# RoverMux.net
KiCad netlist of a schematic drawn in EAGLE
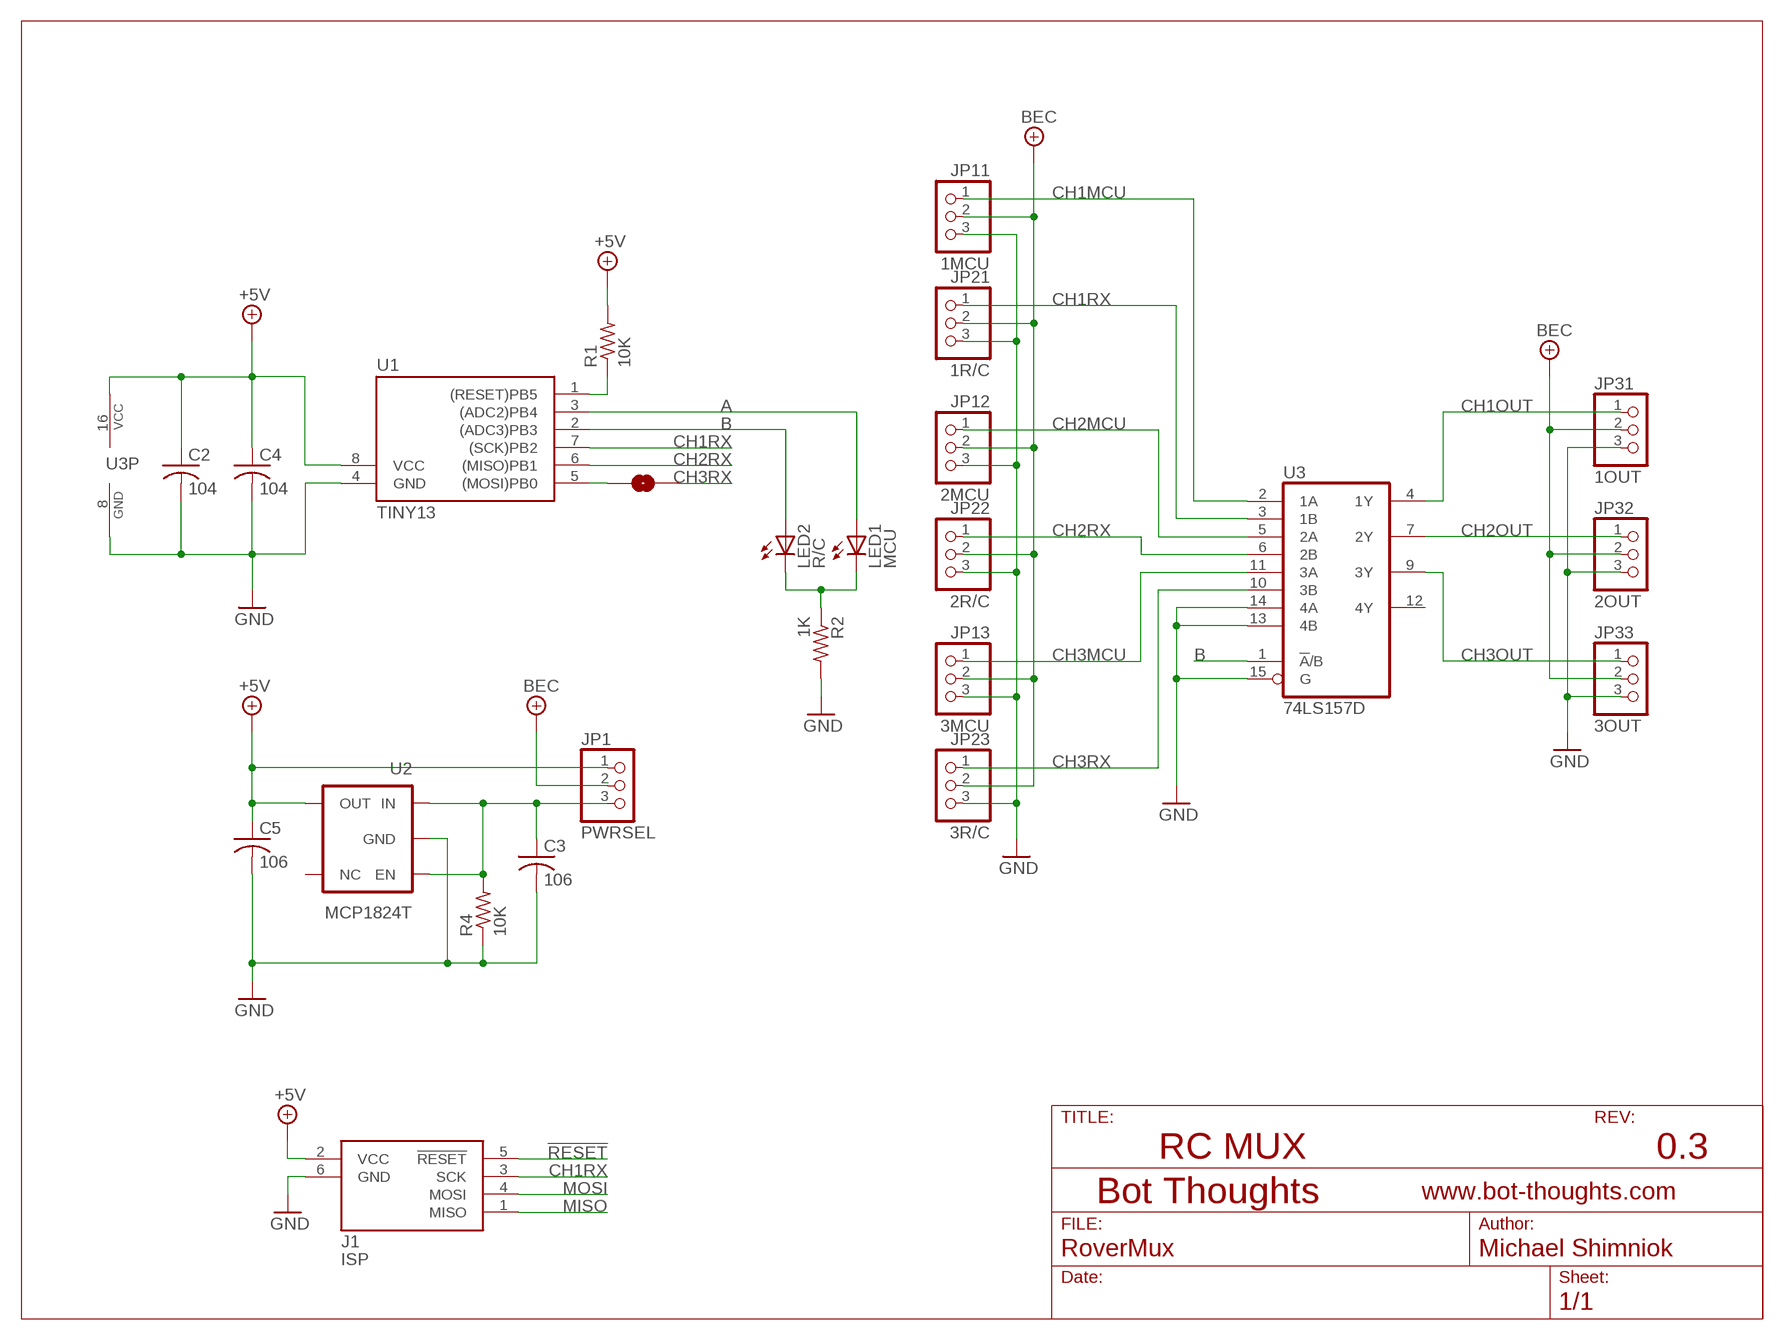
[diagram p0: schematic, sheet 1]

(export (version "E")
  (design (tool "Eeschema 10.0.6"))
  (components
    (comp (ref "C2")
      (value "104")
      (footprint "eagle-import:C0603")
      (fields (field (name "PARTNO") "C1608X7R1E104K080AA"))
      (libsource (lib "eagle-import") (part "C-USC0603"))
    )
    (comp (ref "C3")
      (value "106")
      (footprint "eagle-import:C0603")
      (fields (field (name "PARTNO") "CL10A106MP8NNNC"))
      (libsource (lib "eagle-import") (part "C-USC0603"))
    )
    (comp (ref "C4")
      (value "104")
      (footprint "eagle-import:C0603")
      (fields (field (name "PARTNO") "C1608X7R1E104K080AA"))
      (libsource (lib "eagle-import") (part "C-USC0603"))
    )
    (comp (ref "C5")
      (value "106")
      (footprint "eagle-import:C0603")
      (fields (field (name "PARTNO") "CL10A106MP8NNNC"))
      (libsource (lib "eagle-import") (part "C-USC0603"))
    )
    (comp (ref "J1")
      (value "ISP")
      (footprint "eagle-import:CON6P2R")
      (libsource (lib "eagle-import") (part "AVRISP6"))
    )
    (comp (ref "JP1")
      (value "PWRSEL")
      (footprint "eagle-import:1X03M")
      (libsource (lib "eagle-import") (part "PINHD-1X03_2.00"))
    )
    (comp (ref "JP11")
      (value "1MCU")
      (footprint "eagle-import:1X03-S")
      (libsource (lib "eagle-import") (part "PINHD-1X03_2.54-S"))
    )
    (comp (ref "JP12")
      (value "2MCU")
      (footprint "eagle-import:1X03-S")
      (libsource (lib "eagle-import") (part "PINHD-1X03_2.54-S"))
    )
    (comp (ref "JP13")
      (value "3MCU")
      (footprint "eagle-import:1X03-S")
      (libsource (lib "eagle-import") (part "PINHD-1X03_2.54-S"))
    )
    (comp (ref "JP21")
      (value "1R/C")
      (footprint "eagle-import:1X03-S")
      (libsource (lib "eagle-import") (part "PINHD-1X03_2.54-S"))
    )
    (comp (ref "JP22")
      (value "2R/C")
      (footprint "eagle-import:1X03-S")
      (libsource (lib "eagle-import") (part "PINHD-1X03_2.54-S"))
    )
    (comp (ref "JP23")
      (value "3R/C")
      (footprint "eagle-import:1X03-S")
      (libsource (lib "eagle-import") (part "PINHD-1X03_2.54-S"))
    )
    (comp (ref "JP31")
      (value "1OUT")
      (footprint "eagle-import:1X03-S")
      (libsource (lib "eagle-import") (part "PINHD-1X03_2.54-S"))
    )
    (comp (ref "JP32")
      (value "2OUT")
      (footprint "eagle-import:1X03-S")
      (libsource (lib "eagle-import") (part "PINHD-1X03_2.54-S"))
    )
    (comp (ref "JP33")
      (value "3OUT")
      (footprint "eagle-import:1X03-S")
      (libsource (lib "eagle-import") (part "PINHD-1X03_2.54-S"))
    )
    (comp (ref "LED1")
      (value "MCU")
      (footprint "eagle-import:CHIPLED_1206")
      (fields (field (name "PARTNO") "LH N974-KN-1"))
      (libsource (lib "eagle-import") (part "LEDCHIPLED_1206"))
    )
    (comp (ref "LED2")
      (value "R/C")
      (footprint "eagle-import:CHIPLED_1206")
      (fields (field (name "PARTNO") "LG N971-KN-1"))
      (libsource (lib "eagle-import") (part "LEDCHIPLED_1206"))
    )
    (comp (ref "R1")
      (value "10K")
      (footprint "eagle-import:R0603")
      (fields (field (name "PARTNO") "1622829-1"))
      (libsource (lib "eagle-import") (part "R-US_R0603"))
    )
    (comp (ref "R2")
      (value "1K")
      (footprint "eagle-import:R0603")
      (fields (field (name "PARTNO") "RC0603JR-07330RL"))
      (libsource (lib "eagle-import") (part "R-US_R0603"))
    )
    (comp (ref "R4")
      (value "10K")
      (footprint "eagle-import:R0603")
      (fields (field (name "PARTNO") "1622829-1"))
      (libsource (lib "eagle-import") (part "R-US_R0603"))
    )
    (comp (ref "SJ1")
      (value "CH3")
      (footprint "eagle-import:SJ_2S-NOTRACE")
      (libsource (lib "eagle-import") (part "SOLDERJUMPERNC2"))
    )
    (comp (ref "U1")
      (value "TINY13")
      (footprint "eagle-import:SO08")
      (fields (field (name "PARTNO") "ATTINY13A-SSH"))
      (libsource (lib "eagle-import") (part "TINY138S2"))
    )
    (comp (ref "U2")
      (value "MCP1824T")
      (footprint "eagle-import:SOT23-5")
      (fields (field (name "PARTNO") "MCP1824T-5002E/OT"))
      (libsource (lib "eagle-import") (part "MCP1801"))
    )
    (comp (ref "U3")
      (value "74LS157D")
      (footprint "eagle-import:SO16")
      (fields (field (name "PARTNO") "74HCT157D,652"))
      (libsource (lib "eagle-import") (part "74157DLS"))
    )
  )
  (nets
    (net (code "1") (name "+5V") (class "Default")
      (node (ref "C2") (pin "1") (pinfunction "1_1") (pintype "passive"))
      (node (ref "C4") (pin "1") (pinfunction "1_1") (pintype "passive"))
      (node (ref "C5") (pin "1") (pinfunction "1_1") (pintype "passive"))
      (node (ref "J1") (pin "2") (pinfunction "VCC_2") (pintype "power_in"))
      (node (ref "JP1") (pin "1") (pinfunction "1_1") (pintype "passive"))
      (node (ref "R1") (pin "2") (pinfunction "2_2") (pintype "passive"))
      (node (ref "U1") (pin "8") (pinfunction "VCC_8") (pintype "power_in"))
      (node (ref "U2") (pin "5") (pinfunction "OUT_5") (pintype "passive"))
      (node (ref "U3") (pin "16") (pinfunction "VCC_16") (pintype "power_in"))
    )
    (net (code "2") (name "/A") (class "Default")
      (node (ref "LED1") (pin "A") (pinfunction "A_A") (pintype "passive"))
      (node (ref "U1") (pin "3") (pinfunction "(ADC2)PB4_3") (pintype "bidirectional"))
    )
    (net (code "3") (name "/B") (class "Default")
      (node (ref "LED2") (pin "A") (pinfunction "A_A") (pintype "passive"))
      (node (ref "U1") (pin "2") (pinfunction "(ADC3)PB3_2") (pintype "bidirectional"))
      (node (ref "U3") (pin "1") (pinfunction "~{A}/B_1") (pintype "input"))
    )
    (net (code "4") (name "/CH1MCU") (class "Default")
      (node (ref "JP11") (pin "1") (pinfunction "1_1") (pintype "passive"))
      (node (ref "U3") (pin "2") (pinfunction "1A_2") (pintype "input"))
    )
    (net (code "5") (name "/CH1OUT") (class "Default")
      (node (ref "JP31") (pin "1") (pinfunction "1_1") (pintype "passive"))
      (node (ref "U3") (pin "4") (pinfunction "1Y_4") (pintype "output"))
    )
    (net (code "6") (name "/CH1RX") (class "Default")
      (node (ref "J1") (pin "3") (pinfunction "SCK_3") (pintype "output"))
      (node (ref "JP21") (pin "1") (pinfunction "1_1") (pintype "passive"))
      (node (ref "U1") (pin "7") (pinfunction "(SCK)PB2_7") (pintype "bidirectional"))
      (node (ref "U3") (pin "3") (pinfunction "1B_3") (pintype "input"))
    )
    (net (code "7") (name "/CH2MCU") (class "Default")
      (node (ref "JP12") (pin "1") (pinfunction "1_1") (pintype "passive"))
      (node (ref "U3") (pin "5") (pinfunction "2A_5") (pintype "input"))
    )
    (net (code "8") (name "/CH2OUT") (class "Default")
      (node (ref "JP32") (pin "1") (pinfunction "1_1") (pintype "passive"))
      (node (ref "U3") (pin "7") (pinfunction "2Y_7") (pintype "output"))
    )
    (net (code "9") (name "/CH2RX") (class "Default")
      (node (ref "JP22") (pin "1") (pinfunction "1_1") (pintype "passive"))
      (node (ref "U1") (pin "6") (pinfunction "(MISO)PB1_6") (pintype "bidirectional"))
      (node (ref "U3") (pin "6") (pinfunction "2B_6") (pintype "input"))
    )
    (net (code "10") (name "/CH3MCU") (class "Default")
      (node (ref "JP13") (pin "1") (pinfunction "1_1") (pintype "passive"))
      (node (ref "U3") (pin "11") (pinfunction "3A_11") (pintype "input"))
    )
    (net (code "11") (name "/CH3OUT") (class "Default")
      (node (ref "JP33") (pin "1") (pinfunction "1_1") (pintype "passive"))
      (node (ref "U3") (pin "9") (pinfunction "3Y_9") (pintype "output"))
    )
    (net (code "12") (name "/CH3RX") (class "Default")
      (node (ref "JP23") (pin "1") (pinfunction "1_1") (pintype "passive"))
      (node (ref "SJ1") (pin "2") (pinfunction "2_2") (pintype "passive"))
      (node (ref "U3") (pin "10") (pinfunction "3B_10") (pintype "input"))
    )
    (net (code "13") (name "/MISO") (class "Default")
      (node (ref "J1") (pin "1") (pinfunction "MISO_1") (pintype "input"))
    )
    (net (code "14") (name "/MOSI") (class "Default")
      (node (ref "J1") (pin "4") (pinfunction "MOSI_4") (pintype "output"))
      (node (ref "SJ1") (pin "1") (pinfunction "1_1") (pintype "passive"))
      (node (ref "U1") (pin "5") (pinfunction "(MOSI)PB0_5") (pintype "bidirectional"))
    )
    (net (code "15") (name "/~{RESET}") (class "Default")
      (node (ref "J1") (pin "5") (pinfunction "~{RESET}_5") (pintype "output"))
      (node (ref "R1") (pin "1") (pinfunction "1_1") (pintype "passive"))
      (node (ref "U1") (pin "1") (pinfunction "(RESET)PB5_1") (pintype "bidirectional"))
    )
    (net (code "16") (name "BEC") (class "Default")
      (node (ref "JP1") (pin "2") (pinfunction "2_2") (pintype "passive"))
      (node (ref "JP11") (pin "2") (pinfunction "2_2") (pintype "passive"))
      (node (ref "JP12") (pin "2") (pinfunction "2_2") (pintype "passive"))
      (node (ref "JP13") (pin "2") (pinfunction "2_2") (pintype "passive"))
      (node (ref "JP21") (pin "2") (pinfunction "2_2") (pintype "passive"))
      (node (ref "JP22") (pin "2") (pinfunction "2_2") (pintype "passive"))
      (node (ref "JP23") (pin "2") (pinfunction "2_2") (pintype "passive"))
      (node (ref "JP31") (pin "2") (pinfunction "2_2") (pintype "passive"))
      (node (ref "JP32") (pin "2") (pinfunction "2_2") (pintype "passive"))
      (node (ref "JP33") (pin "2") (pinfunction "2_2") (pintype "passive"))
    )
    (net (code "17") (name "GND") (class "Default")
      (node (ref "C2") (pin "2") (pinfunction "2_2") (pintype "passive"))
      (node (ref "C3") (pin "2") (pinfunction "2_2") (pintype "passive"))
      (node (ref "C4") (pin "2") (pinfunction "2_2") (pintype "passive"))
      (node (ref "C5") (pin "2") (pinfunction "2_2") (pintype "passive"))
      (node (ref "J1") (pin "6") (pinfunction "GND_6") (pintype "power_in"))
      (node (ref "JP11") (pin "3") (pinfunction "3_3") (pintype "passive"))
      (node (ref "JP12") (pin "3") (pinfunction "3_3") (pintype "passive"))
      (node (ref "JP13") (pin "3") (pinfunction "3_3") (pintype "passive"))
      (node (ref "JP21") (pin "3") (pinfunction "3_3") (pintype "passive"))
      (node (ref "JP22") (pin "3") (pinfunction "3_3") (pintype "passive"))
      (node (ref "JP23") (pin "3") (pinfunction "3_3") (pintype "passive"))
      (node (ref "JP31") (pin "3") (pinfunction "3_3") (pintype "passive"))
      (node (ref "JP32") (pin "3") (pinfunction "3_3") (pintype "passive"))
      (node (ref "JP33") (pin "3") (pinfunction "3_3") (pintype "passive"))
      (node (ref "R2") (pin "2") (pinfunction "2_2") (pintype "passive"))
      (node (ref "R4") (pin "1") (pinfunction "1_1") (pintype "passive"))
      (node (ref "U1") (pin "4") (pinfunction "GND_4") (pintype "power_in"))
      (node (ref "U2") (pin "2") (pinfunction "GND_2") (pintype "input"))
      (node (ref "U3") (pin "13") (pinfunction "4B_13") (pintype "input"))
      (node (ref "U3") (pin "14") (pinfunction "4A_14") (pintype "input"))
      (node (ref "U3") (pin "15") (pinfunction "G_15") (pintype "input"))
      (node (ref "U3") (pin "8") (pinfunction "GND_8") (pintype "power_in"))
    )
    (net (code "18") (name "Net-(LED1-PadC)") (class "Default")
      (node (ref "LED1") (pin "C") (pinfunction "C_C") (pintype "passive"))
      (node (ref "LED2") (pin "C") (pinfunction "C_C") (pintype "passive"))
      (node (ref "R2") (pin "1") (pinfunction "1_1") (pintype "passive"))
    )
    (net (code "19") (name "Net-(U2-EN)") (class "Default")
      (node (ref "C3") (pin "1") (pinfunction "1_1") (pintype "passive"))
      (node (ref "JP1") (pin "3") (pinfunction "3_3") (pintype "passive"))
      (node (ref "R4") (pin "2") (pinfunction "2_2") (pintype "passive"))
      (node (ref "U2") (pin "1") (pinfunction "IN_1") (pintype "input"))
      (node (ref "U2") (pin "3") (pinfunction "EN_3") (pintype "input"))
    )
    (net (code "20") (name "unconnected-(U2-NC-Pad4)") (class "Default")
      (node (ref "U2") (pin "4") (pinfunction "NC_4") (pintype "input"))
    )
    (net (code "21") (name "unconnected-(U3A-4Y-Pad12)") (class "Default")
      (node (ref "U3") (pin "12") (pinfunction "4Y_12") (pintype "output"))
    )
  )
)
